# Temperatura_y_humedad.net
KiCad netlist of a schematic drawn in EAGLE
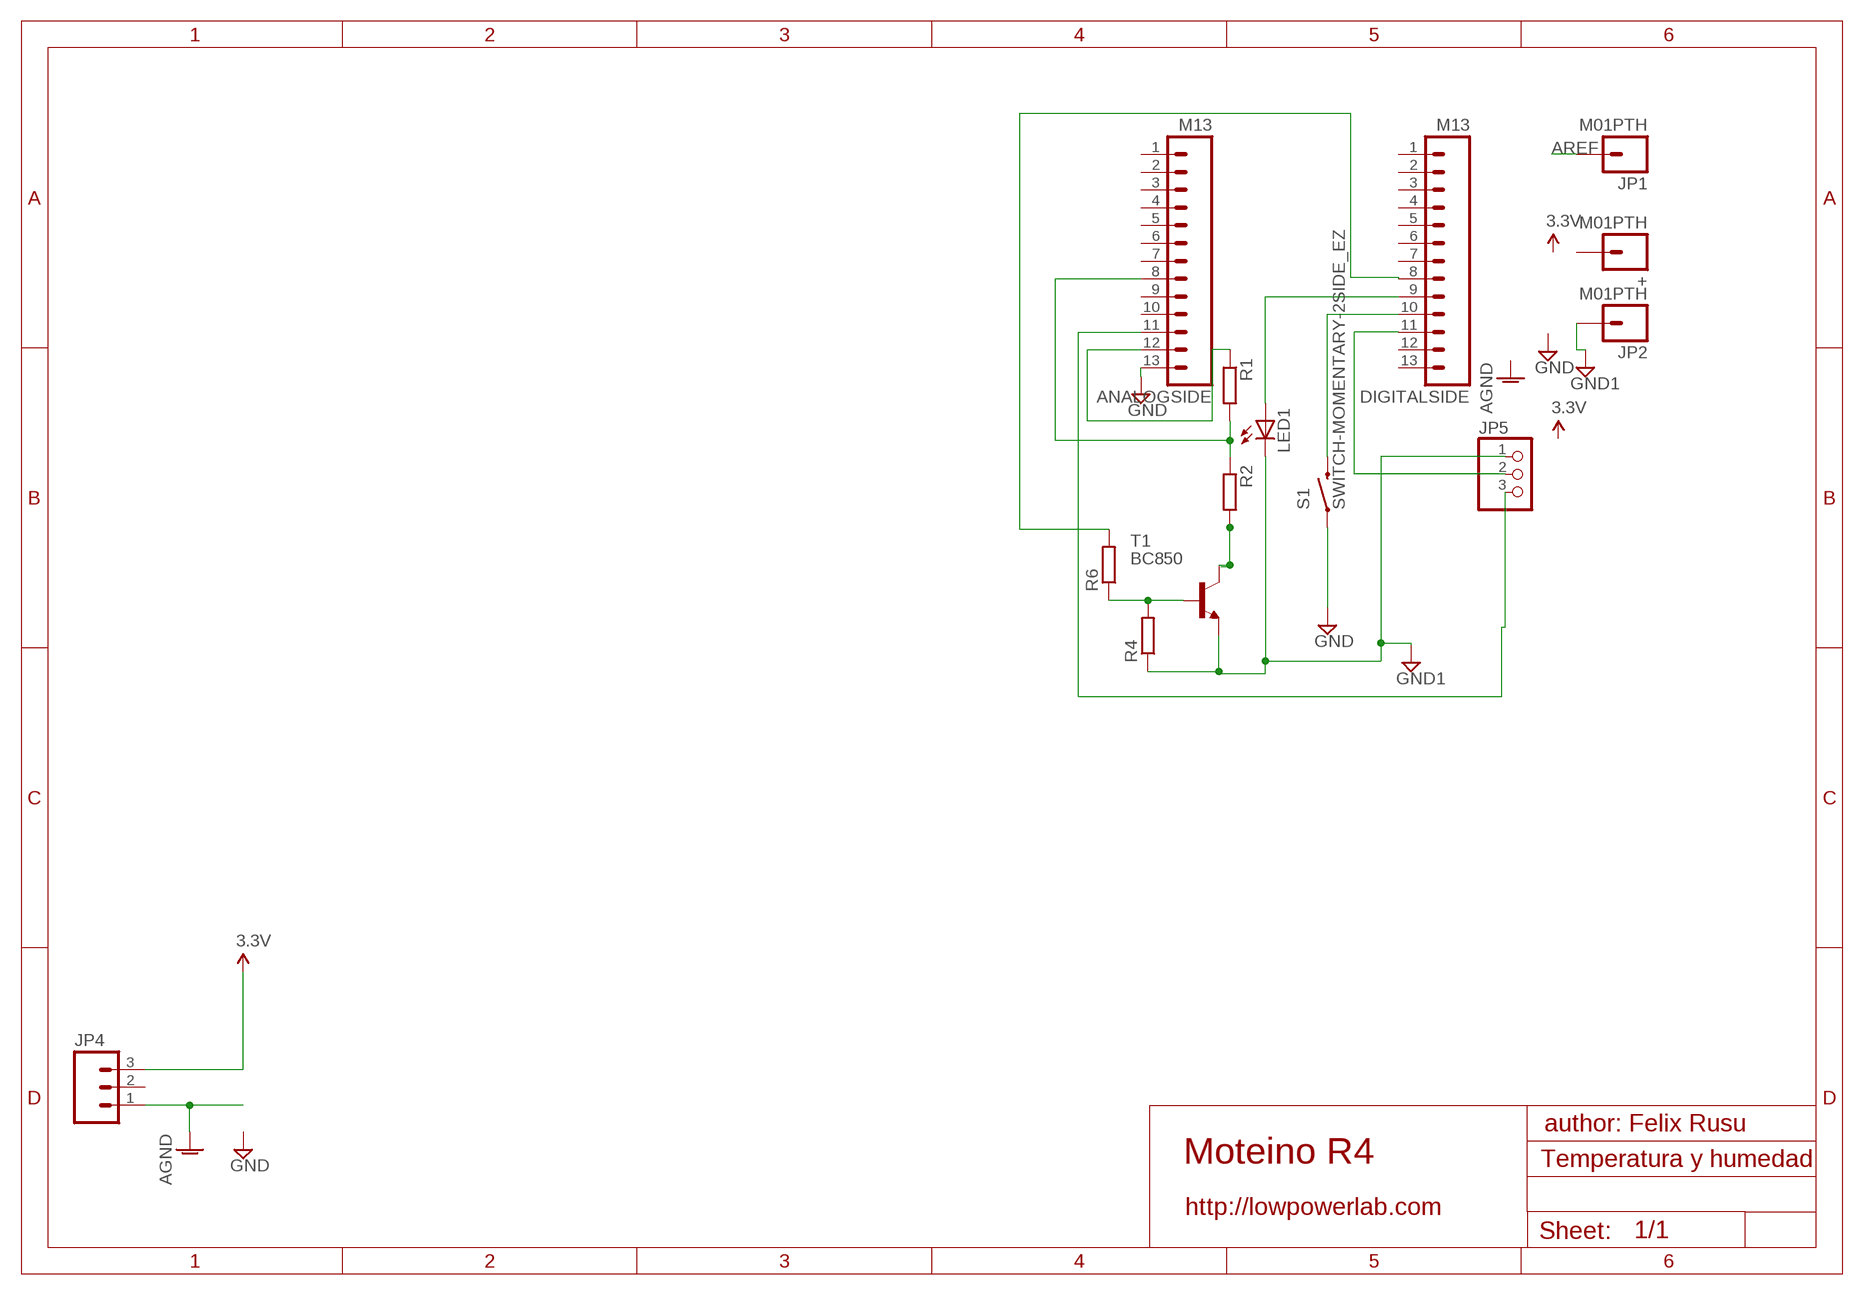
[diagram p0: schematic, sheet 1]

(export (version "E")
  (design (tool "Eeschema 10.0.6"))
  (components
    (comp (ref "+")
      (value "M01PTH")
      (footprint "eagle-import:1X01")
      (libsource (lib "eagle-import") (part "M01PTH"))
    )
    (comp (ref "ANALOGSIDE")
      (value "M13")
      (footprint "eagle-import:1X13")
      (libsource (lib "eagle-import") (part "M13"))
    )
    (comp (ref "DIGITALSIDE")
      (value "M13")
      (footprint "eagle-import:1X13")
      (libsource (lib "eagle-import") (part "M13"))
    )
    (comp (ref "JP1")
      (value "M01PTH")
      (footprint "eagle-import:1X01")
      (libsource (lib "eagle-import") (part "M01PTH"))
    )
    (comp (ref "JP2")
      (value "M01PTH")
      (footprint "eagle-import:1X01")
      (libsource (lib "eagle-import") (part "M01PTH"))
    )
    (comp (ref "JP4")
      (value "M03PTH")
      (footprint "eagle-import:1X03")
      (libsource (lib "eagle-import") (part "M03PTH"))
    )
    (comp (ref "JP5")
      (value "PINHD-1X3")
      (footprint "eagle-import:1X03")
      (libsource (lib "eagle-import") (part "PINHD-1X3"))
    )
    (comp (ref "LED1")
      (value "LED3MM")
      (footprint "eagle-import:LED3MM")
      (libsource (lib "eagle-import") (part "LED3MM"))
    )
    (comp (ref "R1")
      (value "R-EU_0204/7")
      (footprint "eagle-import:0204_7")
      (libsource (lib "eagle-import") (part "R-EU_0204/7"))
    )
    (comp (ref "R2")
      (value "R-EU_0204/7")
      (footprint "eagle-import:0204_7")
      (libsource (lib "eagle-import") (part "R-EU_0204/7"))
    )
    (comp (ref "R4")
      (value "R-EU_M1206")
      (footprint "eagle-import:M1206")
      (libsource (lib "eagle-import") (part "R-EU_M1206"))
    )
    (comp (ref "R6")
      (value "R-EU_M1206")
      (footprint "eagle-import:M1206")
      (libsource (lib "eagle-import") (part "R-EU_M1206"))
    )
    (comp (ref "S1")
      (value "SWITCH-MOMENTARY-2SIDE_EZ")
      (footprint "eagle-import:TACTILE-PTH-SIDEEZ")
      (libsource (lib "eagle-import") (part "SWITCH-MOMENTARY-2SIDE_EZ"))
    )
    (comp (ref "T1")
      (value "BC850")
      (footprint "eagle-import:SOT23")
      (libsource (lib "eagle-import") (part "BC850"))
    )
  )
  (nets
    (net (code "1") (name "/AREF") (class "Default")
      (node (ref "JP1") (pin "1") (pinfunction "1_1") (pintype "passive"))
    )
    (net (code "2") (name "3.3V") (class "Default")
      (node (ref "JP4") (pin "3") (pinfunction "3_3") (pintype "passive"))
    )
    (net (code "3") (name "AGND") (class "Default")
      (node (ref "JP4") (pin "1") (pinfunction "1_1") (pintype "passive"))
    )
    (net (code "4") (name "GND") (class "Default")
      (node (ref "ANALOGSIDE") (pin "13") (pinfunction "13_13") (pintype "passive"))
      (node (ref "S1") (pin "1") (pinfunction "1_1") (pintype "passive"))
    )
    (net (code "5") (name "GND1") (class "Default")
      (node (ref "JP2") (pin "1") (pinfunction "1_1") (pintype "passive"))
      (node (ref "JP5") (pin "1") (pinfunction "1_1") (pintype "passive"))
      (node (ref "LED1") (pin "K") (pinfunction "C_K") (pintype "passive"))
      (node (ref "R4") (pin "1") (pinfunction "1_1") (pintype "passive"))
      (node (ref "T1") (pin "2") (pinfunction "E_2") (pintype "passive"))
    )
    (net (code "6") (name "Net-(ANALOGSIDE-Pad8)") (class "Default")
      (node (ref "ANALOGSIDE") (pin "8") (pinfunction "8_8") (pintype "passive"))
      (node (ref "R1") (pin "2") (pinfunction "2_2") (pintype "passive"))
      (node (ref "R2") (pin "1") (pinfunction "1_1") (pintype "passive"))
    )
    (net (code "7") (name "Net-(ANALOGSIDE-Pad11)") (class "Default")
      (node (ref "ANALOGSIDE") (pin "11") (pinfunction "11_11") (pintype "passive"))
      (node (ref "JP5") (pin "3") (pinfunction "3_3") (pintype "passive"))
    )
    (net (code "8") (name "Net-(ANALOGSIDE-Pad12)") (class "Default")
      (node (ref "ANALOGSIDE") (pin "12") (pinfunction "12_12") (pintype "passive"))
      (node (ref "R1") (pin "1") (pinfunction "1_1") (pintype "passive"))
    )
    (net (code "9") (name "Net-(DIGITALSIDE-Pad8)") (class "Default")
      (node (ref "DIGITALSIDE") (pin "8") (pinfunction "8_8") (pintype "passive"))
      (node (ref "R6") (pin "2") (pinfunction "2_2") (pintype "passive"))
    )
    (net (code "10") (name "Net-(DIGITALSIDE-Pad9)") (class "Default")
      (node (ref "DIGITALSIDE") (pin "9") (pinfunction "9_9") (pintype "passive"))
      (node (ref "LED1") (pin "A") (pinfunction "A_A") (pintype "passive"))
    )
    (net (code "11") (name "Net-(DIGITALSIDE-Pad10)") (class "Default")
      (node (ref "DIGITALSIDE") (pin "10") (pinfunction "10_10") (pintype "passive"))
      (node (ref "S1") (pin "2") (pinfunction "2_2") (pintype "passive"))
    )
    (net (code "12") (name "Net-(DIGITALSIDE-Pad11)") (class "Default")
      (node (ref "DIGITALSIDE") (pin "11") (pinfunction "11_11") (pintype "passive"))
      (node (ref "JP5") (pin "2") (pinfunction "2_2") (pintype "passive"))
    )
    (net (code "13") (name "Net-(T1-B)") (class "Default")
      (node (ref "R4") (pin "2") (pinfunction "2_2") (pintype "passive"))
      (node (ref "R6") (pin "1") (pinfunction "1_1") (pintype "passive"))
      (node (ref "T1") (pin "1") (pinfunction "B_1") (pintype "passive"))
    )
    (net (code "14") (name "Net-(T1-C)") (class "Default")
      (node (ref "R2") (pin "2") (pinfunction "2_2") (pintype "passive"))
      (node (ref "T1") (pin "3") (pinfunction "C_3") (pintype "passive"))
    )
    (net (code "15") (name "unconnected-(+-Pad1)") (class "Default")
      (node (ref "+") (pin "1") (pinfunction "1_1") (pintype "passive"))
    )
    (net (code "16") (name "unconnected-(ANALOGSIDE-Pad1)") (class "Default")
      (node (ref "ANALOGSIDE") (pin "1") (pinfunction "1_1") (pintype "passive"))
    )
    (net (code "17") (name "unconnected-(ANALOGSIDE-Pad2)") (class "Default")
      (node (ref "ANALOGSIDE") (pin "2") (pinfunction "2_2") (pintype "passive"))
    )
    (net (code "18") (name "unconnected-(ANALOGSIDE-Pad3)") (class "Default")
      (node (ref "ANALOGSIDE") (pin "3") (pinfunction "3_3") (pintype "passive"))
    )
    (net (code "19") (name "unconnected-(ANALOGSIDE-Pad4)") (class "Default")
      (node (ref "ANALOGSIDE") (pin "4") (pinfunction "4_4") (pintype "passive"))
    )
    (net (code "20") (name "unconnected-(ANALOGSIDE-Pad5)") (class "Default")
      (node (ref "ANALOGSIDE") (pin "5") (pinfunction "5_5") (pintype "passive"))
    )
    (net (code "21") (name "unconnected-(ANALOGSIDE-Pad6)") (class "Default")
      (node (ref "ANALOGSIDE") (pin "6") (pinfunction "6_6") (pintype "passive"))
    )
    (net (code "22") (name "unconnected-(ANALOGSIDE-Pad7)") (class "Default")
      (node (ref "ANALOGSIDE") (pin "7") (pinfunction "7_7") (pintype "passive"))
    )
    (net (code "23") (name "unconnected-(ANALOGSIDE-Pad9)") (class "Default")
      (node (ref "ANALOGSIDE") (pin "9") (pinfunction "9_9") (pintype "passive"))
    )
    (net (code "24") (name "unconnected-(ANALOGSIDE-Pad10)") (class "Default")
      (node (ref "ANALOGSIDE") (pin "10") (pinfunction "10_10") (pintype "passive"))
    )
    (net (code "25") (name "unconnected-(DIGITALSIDE-Pad1)") (class "Default")
      (node (ref "DIGITALSIDE") (pin "1") (pinfunction "1_1") (pintype "passive"))
    )
    (net (code "26") (name "unconnected-(DIGITALSIDE-Pad2)") (class "Default")
      (node (ref "DIGITALSIDE") (pin "2") (pinfunction "2_2") (pintype "passive"))
    )
    (net (code "27") (name "unconnected-(DIGITALSIDE-Pad3)") (class "Default")
      (node (ref "DIGITALSIDE") (pin "3") (pinfunction "3_3") (pintype "passive"))
    )
    (net (code "28") (name "unconnected-(DIGITALSIDE-Pad4)") (class "Default")
      (node (ref "DIGITALSIDE") (pin "4") (pinfunction "4_4") (pintype "passive"))
    )
    (net (code "29") (name "unconnected-(DIGITALSIDE-Pad5)") (class "Default")
      (node (ref "DIGITALSIDE") (pin "5") (pinfunction "5_5") (pintype "passive"))
    )
    (net (code "30") (name "unconnected-(DIGITALSIDE-Pad6)") (class "Default")
      (node (ref "DIGITALSIDE") (pin "6") (pinfunction "6_6") (pintype "passive"))
    )
    (net (code "31") (name "unconnected-(DIGITALSIDE-Pad7)") (class "Default")
      (node (ref "DIGITALSIDE") (pin "7") (pinfunction "7_7") (pintype "passive"))
    )
    (net (code "32") (name "unconnected-(DIGITALSIDE-Pad12)") (class "Default")
      (node (ref "DIGITALSIDE") (pin "12") (pinfunction "12_12") (pintype "passive"))
    )
    (net (code "33") (name "unconnected-(DIGITALSIDE-Pad13)") (class "Default")
      (node (ref "DIGITALSIDE") (pin "13") (pinfunction "13_13") (pintype "passive"))
    )
    (net (code "34") (name "unconnected-(JP4-Pad2)") (class "Default")
      (node (ref "JP4") (pin "2") (pinfunction "2_2") (pintype "passive"))
    )
  )
)
